# main-board_v1_23.net
KiCad netlist of a schematic drawn in EAGLE
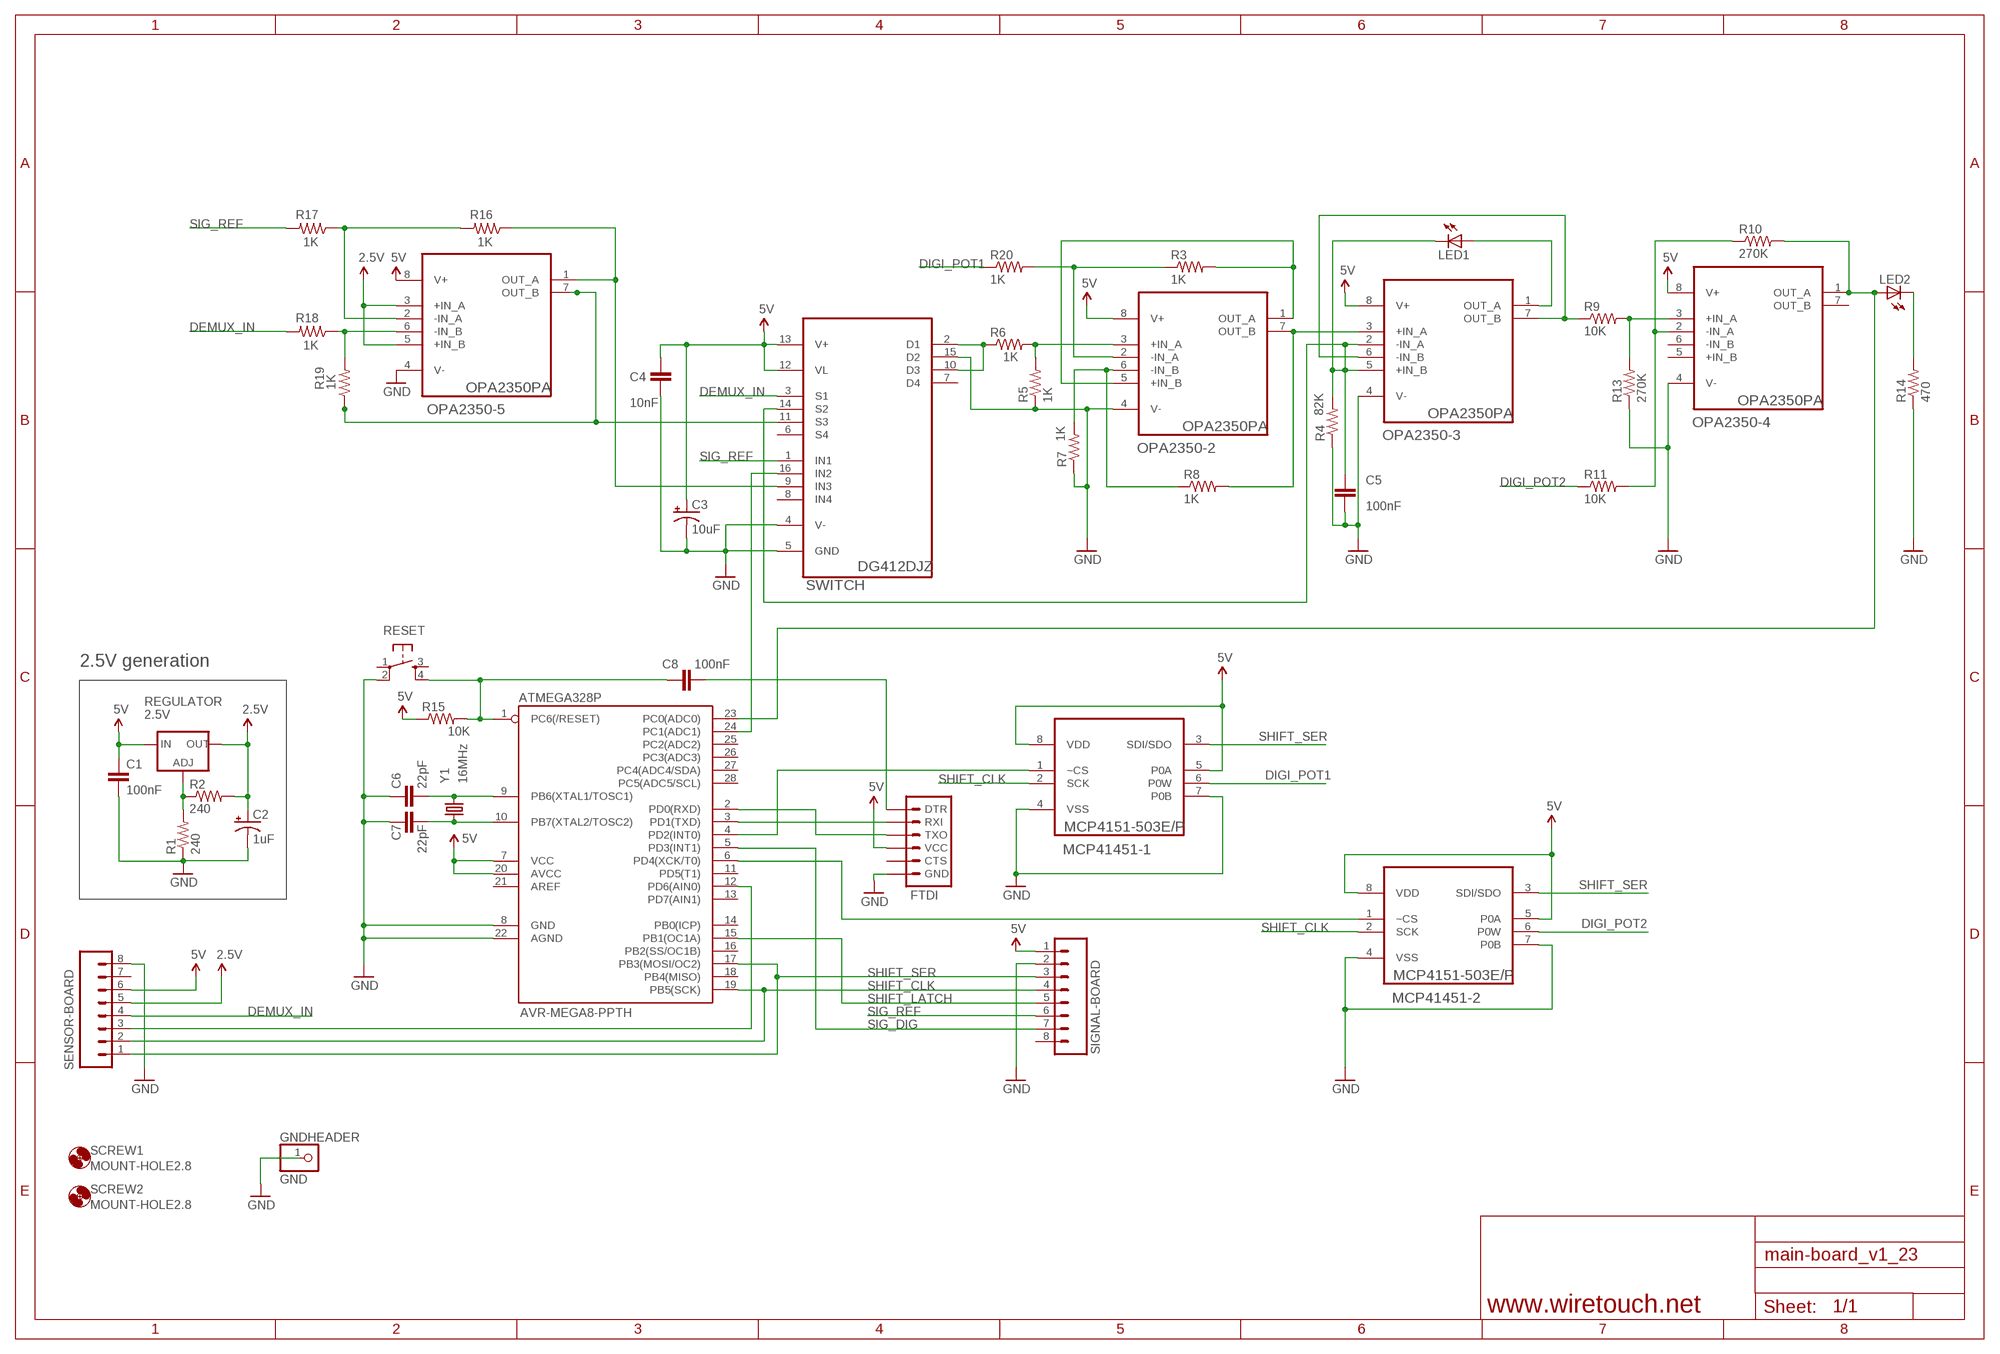
[diagram p0: schematic, sheet 1]

(export (version "E")
  (design (tool "Eeschema 10.0.6"))
  (components
    (comp (ref "ATMEGA328P")
      (value "AVR-MEGA8-PPTH")
      (footprint "eagle-import:DIL28-3")
      (libsource (lib "eagle-import") (part "AVR-MEGA8-PPTH"))
    )
    (comp (ref "C1")
      (value "100nF")
      (footprint "eagle-import:CAP-PTH-SMALL")
      (libsource (lib "eagle-import") (part "CAPPTH"))
    )
    (comp (ref "C2")
      (value "1uF")
      (footprint "eagle-import:CPOL-RADIAL-10UF-25V")
      (libsource (lib "eagle-import") (part "CAP_POLPTH2"))
    )
    (comp (ref "C3")
      (value "10uF")
      (footprint "eagle-import:CPOL-RADIAL-10UF-25V")
      (libsource (lib "eagle-import") (part "CAP_POLPTH2"))
    )
    (comp (ref "C4")
      (value "10nF")
      (footprint "eagle-import:CAP-PTH-SMALL")
      (libsource (lib "eagle-import") (part "CAPPTH"))
    )
    (comp (ref "C5")
      (value "100nF")
      (footprint "eagle-import:CAP-PTH-SMALL")
      (libsource (lib "eagle-import") (part "CAPPTH"))
    )
    (comp (ref "C6")
      (value "22pF")
      (footprint "eagle-import:CAP-PTH-SMALL2")
      (libsource (lib "eagle-import") (part "CAPPTH2"))
    )
    (comp (ref "C7")
      (value "22pF")
      (footprint "eagle-import:CAP-PTH-SMALL2")
      (libsource (lib "eagle-import") (part "CAPPTH2"))
    )
    (comp (ref "C8")
      (value "100nF")
      (footprint "eagle-import:CAP-PTH-SMALL2")
      (libsource (lib "eagle-import") (part "CAPPTH2"))
    )
    (comp (ref "FTDI")
      (value "ARDUINO_SERIAL_PROGRAMLONGPADS")
      (footprint "eagle-import:1X06_LONGPADS")
      (libsource (lib "eagle-import") (part "ARDUINO_SERIAL_PROGRAMLONGPADS"))
    )
    (comp (ref "GNDHEADER")
      (value "GND")
      (footprint "eagle-import:1X01")
      (libsource (lib "eagle-import") (part "PINHD-1X1"))
    )
    (comp (ref "LED1")
      (value "LED3MM")
      (footprint "eagle-import:LED3MM")
      (libsource (lib "eagle-import") (part "LED3MM"))
    )
    (comp (ref "LED2")
      (value "LED5MM")
      (footprint "eagle-import:LED5MM")
      (libsource (lib "eagle-import") (part "LED5MM"))
    )
    (comp (ref "MCP41451-1")
      (value "MCP4151-503E/P")
      (footprint "eagle-import:DIP254P762X533-8")
      (libsource (lib "eagle-import") (part "MCP4151-503E/P"))
    )
    (comp (ref "MCP41451-2")
      (value "MCP4151-503E/P")
      (footprint "eagle-import:DIP254P762X533-8")
      (libsource (lib "eagle-import") (part "MCP4151-503E/P"))
    )
    (comp (ref "OPA2350-2")
      (value "OPA2350PA")
      (footprint "eagle-import:DIP254P762X508-8")
      (libsource (lib "eagle-import") (part "OPA2350PA"))
    )
    (comp (ref "OPA2350-3")
      (value "OPA2350PA")
      (footprint "eagle-import:DIP254P762X508-8")
      (libsource (lib "eagle-import") (part "OPA2350PA"))
    )
    (comp (ref "OPA2350-4")
      (value "OPA2350PA")
      (footprint "eagle-import:DIP254P762X508-8")
      (libsource (lib "eagle-import") (part "OPA2350PA"))
    )
    (comp (ref "OPA2350-5")
      (value "OPA2350PA")
      (footprint "eagle-import:DIP254P762X508-8")
      (libsource (lib "eagle-import") (part "OPA2350PA"))
    )
    (comp (ref "R1")
      (value "240")
      (footprint "eagle-import:AXIAL-0.3")
      (libsource (lib "eagle-import") (part "RESISTORAXIAL-0.3"))
    )
    (comp (ref "R2")
      (value "240")
      (footprint "eagle-import:AXIAL-0.3")
      (libsource (lib "eagle-import") (part "RESISTORAXIAL-0.3"))
    )
    (comp (ref "R3")
      (value "1K")
      (footprint "eagle-import:AXIAL-0.3")
      (libsource (lib "eagle-import") (part "RESISTORAXIAL-0.3"))
    )
    (comp (ref "R4")
      (value "82K")
      (footprint "eagle-import:AXIAL-0.3")
      (libsource (lib "eagle-import") (part "RESISTORAXIAL-0.3"))
    )
    (comp (ref "R5")
      (value "1K")
      (footprint "eagle-import:AXIAL-0.3")
      (libsource (lib "eagle-import") (part "RESISTORAXIAL-0.3"))
    )
    (comp (ref "R6")
      (value "1K")
      (footprint "eagle-import:AXIAL-0.3")
      (libsource (lib "eagle-import") (part "RESISTORAXIAL-0.3"))
    )
    (comp (ref "R7")
      (value "1K")
      (footprint "eagle-import:AXIAL-0.3")
      (libsource (lib "eagle-import") (part "RESISTORAXIAL-0.3"))
    )
    (comp (ref "R8")
      (value "1K")
      (footprint "eagle-import:AXIAL-0.3")
      (libsource (lib "eagle-import") (part "RESISTORAXIAL-0.3"))
    )
    (comp (ref "R9")
      (value "10K")
      (footprint "eagle-import:AXIAL-0.3")
      (libsource (lib "eagle-import") (part "RESISTORAXIAL-0.3"))
    )
    (comp (ref "R10")
      (value "270K")
      (footprint "eagle-import:AXIAL-0.3")
      (libsource (lib "eagle-import") (part "RESISTORAXIAL-0.3"))
    )
    (comp (ref "R11")
      (value "10K")
      (footprint "eagle-import:AXIAL-0.3")
      (libsource (lib "eagle-import") (part "RESISTORAXIAL-0.3"))
    )
    (comp (ref "R13")
      (value "270K")
      (footprint "eagle-import:AXIAL-0.3")
      (libsource (lib "eagle-import") (part "RESISTORAXIAL-0.3"))
    )
    (comp (ref "R14")
      (value "470")
      (footprint "eagle-import:AXIAL-0.3")
      (libsource (lib "eagle-import") (part "RESISTORAXIAL-0.3"))
    )
    (comp (ref "R15")
      (value "10K")
      (footprint "eagle-import:AXIAL-0.3")
      (libsource (lib "eagle-import") (part "RESISTORAXIAL-0.3"))
    )
    (comp (ref "R16")
      (value "1K")
      (footprint "eagle-import:AXIAL-0.3")
      (libsource (lib "eagle-import") (part "RESISTORAXIAL-0.3"))
    )
    (comp (ref "R17")
      (value "1K")
      (footprint "eagle-import:AXIAL-0.3")
      (libsource (lib "eagle-import") (part "RESISTORAXIAL-0.3"))
    )
    (comp (ref "R18")
      (value "1K")
      (footprint "eagle-import:AXIAL-0.3")
      (libsource (lib "eagle-import") (part "RESISTORAXIAL-0.3"))
    )
    (comp (ref "R19")
      (value "1K")
      (footprint "eagle-import:AXIAL-0.3")
      (libsource (lib "eagle-import") (part "RESISTORAXIAL-0.3"))
    )
    (comp (ref "R20")
      (value "1K")
      (footprint "eagle-import:AXIAL-0.3")
      (libsource (lib "eagle-import") (part "RESISTORAXIAL-0.3"))
    )
    (comp (ref "REGULATOR")
      (value "2.5V")
      (footprint "eagle-import:TO220-ADJ")
      (libsource (lib "eagle-import") (part "V_REG_317SINK"))
    )
    (comp (ref "RESET")
      (value "Omron B3F momentary on switch")
      (footprint "eagle-import:TACTILE-PTH")
      (libsource (lib "eagle-import") (part "TAC_SWITCHPTH"))
    )
    (comp (ref "SCREW1")
      (value "MOUNT-HOLE2.8")
      (footprint "eagle-import:2,8")
      (libsource (lib "eagle-import") (part "MOUNT-HOLE2.8"))
    )
    (comp (ref "SCREW2")
      (value "MOUNT-HOLE2.8")
      (footprint "eagle-import:2,8")
      (libsource (lib "eagle-import") (part "MOUNT-HOLE2.8"))
    )
    (comp (ref "SENSOR-BOARD")
      (value "M08LONGPADS")
      (footprint "eagle-import:1X08_LONGPADS")
      (libsource (lib "eagle-import") (part "M08LONGPADS"))
    )
    (comp (ref "SIGNAL-BOARD")
      (value "M08LONGPADS")
      (footprint "eagle-import:1X08_LONGPADS")
      (libsource (lib "eagle-import") (part "M08LONGPADS"))
    )
    (comp (ref "SWITCH")
      (value "DG412DJZ")
      (footprint "eagle-import:DIP254P762X533-16")
      (libsource (lib "eagle-import") (part "DG412DJZ"))
    )
    (comp (ref "Y1")
      (value "16MHz")
      (footprint "eagle-import:HC49US")
      (libsource (lib "eagle-import") (part "CRYSTALHC49US"))
    )
  )
  (nets
    (net (code "1") (name "/DEMUX_IN") (class "Default")
      (node (ref "R18") (pin "P$2") (pinfunction "2_P$2") (pintype "passive"))
      (node (ref "SENSOR-BOARD") (pin "4") (pinfunction "4_4") (pintype "passive"))
      (node (ref "SWITCH") (pin "3") (pinfunction "S1_3") (pintype "input"))
    )
    (net (code "2") (name "/DIGI_POT1") (class "Default")
      (node (ref "MCP41451-1") (pin "6") (pinfunction "P0W_6") (pintype "passive"))
      (node (ref "R20") (pin "P$1") (pinfunction "1_P$1") (pintype "passive"))
    )
    (net (code "3") (name "/DIGI_POT2") (class "Default")
      (node (ref "MCP41451-2") (pin "6") (pinfunction "P0W_6") (pintype "passive"))
      (node (ref "R11") (pin "P$1") (pinfunction "1_P$1") (pintype "passive"))
    )
    (net (code "4") (name "/SHIFT_CLK") (class "Default")
      (node (ref "ATMEGA328P") (pin "19") (pinfunction "PB5(SCK)_19") (pintype "bidirectional"))
      (node (ref "MCP41451-1") (pin "2") (pinfunction "SCK_2") (pintype "input"))
      (node (ref "MCP41451-2") (pin "2") (pinfunction "SCK_2") (pintype "input"))
      (node (ref "SENSOR-BOARD") (pin "2") (pinfunction "2_2") (pintype "passive"))
      (node (ref "SIGNAL-BOARD") (pin "4") (pinfunction "4_4") (pintype "passive"))
    )
    (net (code "5") (name "/SHIFT_LATCH") (class "Default")
      (node (ref "ATMEGA328P") (pin "15") (pinfunction "PB1(OC1A)_15") (pintype "bidirectional"))
      (node (ref "SIGNAL-BOARD") (pin "5") (pinfunction "5_5") (pintype "passive"))
    )
    (net (code "6") (name "/SHIFT_SER") (class "Default")
      (node (ref "ATMEGA328P") (pin "17") (pinfunction "PB3(MOSI/OC2)_17") (pintype "bidirectional"))
      (node (ref "MCP41451-1") (pin "3") (pinfunction "SDI/SDO_3") (pintype "bidirectional"))
      (node (ref "MCP41451-2") (pin "3") (pinfunction "SDI/SDO_3") (pintype "bidirectional"))
      (node (ref "SENSOR-BOARD") (pin "1") (pinfunction "1_1") (pintype "passive"))
      (node (ref "SIGNAL-BOARD") (pin "3") (pinfunction "3_3") (pintype "passive"))
    )
    (net (code "7") (name "/SIG_DIG") (class "Default")
      (node (ref "ATMEGA328P") (pin "5") (pinfunction "PD3(INT1)_5") (pintype "bidirectional"))
      (node (ref "SIGNAL-BOARD") (pin "7") (pinfunction "7_7") (pintype "passive"))
    )
    (net (code "8") (name "/SIG_REF") (class "Default")
      (node (ref "R17") (pin "P$2") (pinfunction "2_P$2") (pintype "passive"))
      (node (ref "SIGNAL-BOARD") (pin "6") (pinfunction "6_6") (pintype "passive"))
      (node (ref "SWITCH") (pin "1") (pinfunction "IN1_1") (pintype "input"))
    )
    (net (code "9") (name "2.5V") (class "Default")
      (node (ref "C2") (pin "1") (pinfunction "+_1") (pintype "passive"))
      (node (ref "OPA2350-5") (pin "3") (pinfunction "+IN_A_3") (pintype "input"))
      (node (ref "OPA2350-5") (pin "5") (pinfunction "+IN_B_5") (pintype "input"))
      (node (ref "R2") (pin "P$2") (pinfunction "2_P$2") (pintype "passive"))
      (node (ref "REGULATOR") (pin "OUT") (pinfunction "OUT_OUT") (pintype "output"))
      (node (ref "SENSOR-BOARD") (pin "5") (pinfunction "5_5") (pintype "passive"))
    )
    (net (code "10") (name "5V") (class "Default")
      (node (ref "ATMEGA328P") (pin "20") (pinfunction "AVCC_20") (pintype "bidirectional"))
      (node (ref "ATMEGA328P") (pin "7") (pinfunction "VCC_7") (pintype "bidirectional"))
      (node (ref "C1") (pin "1") (pinfunction "1_1") (pintype "passive"))
      (node (ref "C3") (pin "1") (pinfunction "+_1") (pintype "passive"))
      (node (ref "C4") (pin "1") (pinfunction "1_1") (pintype "passive"))
      (node (ref "FTDI") (pin "4") (pinfunction "VCC_4") (pintype "passive"))
      (node (ref "MCP41451-1") (pin "5") (pinfunction "P0A_5") (pintype "passive"))
      (node (ref "MCP41451-1") (pin "8") (pinfunction "VDD_8") (pintype "power_in"))
      (node (ref "MCP41451-2") (pin "5") (pinfunction "P0A_5") (pintype "passive"))
      (node (ref "MCP41451-2") (pin "8") (pinfunction "VDD_8") (pintype "power_in"))
      (node (ref "OPA2350-2") (pin "8") (pinfunction "V+_8") (pintype "power_in"))
      (node (ref "OPA2350-3") (pin "8") (pinfunction "V+_8") (pintype "power_in"))
      (node (ref "OPA2350-4") (pin "8") (pinfunction "V+_8") (pintype "power_in"))
      (node (ref "OPA2350-5") (pin "8") (pinfunction "V+_8") (pintype "power_in"))
      (node (ref "R15") (pin "P$1") (pinfunction "1_P$1") (pintype "passive"))
      (node (ref "REGULATOR") (pin "IN") (pinfunction "IN_IN") (pintype "input"))
      (node (ref "SENSOR-BOARD") (pin "6") (pinfunction "6_6") (pintype "passive"))
      (node (ref "SIGNAL-BOARD") (pin "1") (pinfunction "1_1") (pintype "passive"))
      (node (ref "SWITCH") (pin "12") (pinfunction "VL_12") (pintype "power_in"))
      (node (ref "SWITCH") (pin "13") (pinfunction "V+_13") (pintype "power_in"))
    )
    (net (code "11") (name "GND") (class "Default")
      (node (ref "ATMEGA328P") (pin "22") (pinfunction "AGND_22") (pintype "bidirectional"))
      (node (ref "ATMEGA328P") (pin "8") (pinfunction "GND_8") (pintype "bidirectional"))
      (node (ref "C1") (pin "2") (pinfunction "2_2") (pintype "passive"))
      (node (ref "C2") (pin "2") (pinfunction "-_2") (pintype "passive"))
      (node (ref "C3") (pin "2") (pinfunction "-_2") (pintype "passive"))
      (node (ref "C4") (pin "2") (pinfunction "2_2") (pintype "passive"))
      (node (ref "C5") (pin "2") (pinfunction "2_2") (pintype "passive"))
      (node (ref "C6") (pin "1") (pinfunction "1_1") (pintype "passive"))
      (node (ref "C7") (pin "1") (pinfunction "1_1") (pintype "passive"))
      (node (ref "FTDI") (pin "6") (pinfunction "GND_6") (pintype "passive"))
      (node (ref "GNDHEADER") (pin "1") (pinfunction "1_1") (pintype "passive"))
      (node (ref "MCP41451-1") (pin "4") (pinfunction "VSS_4") (pintype "power_in"))
      (node (ref "MCP41451-1") (pin "7") (pinfunction "P0B_7") (pintype "passive"))
      (node (ref "MCP41451-2") (pin "4") (pinfunction "VSS_4") (pintype "power_in"))
      (node (ref "MCP41451-2") (pin "7") (pinfunction "P0B_7") (pintype "passive"))
      (node (ref "OPA2350-2") (pin "4") (pinfunction "V-_4") (pintype "power_in"))
      (node (ref "OPA2350-3") (pin "4") (pinfunction "V-_4") (pintype "power_in"))
      (node (ref "OPA2350-4") (pin "4") (pinfunction "V-_4") (pintype "power_in"))
      (node (ref "OPA2350-5") (pin "4") (pinfunction "V-_4") (pintype "power_in"))
      (node (ref "R1") (pin "P$1") (pinfunction "1_P$1") (pintype "passive"))
      (node (ref "R13") (pin "P$1") (pinfunction "1_P$1") (pintype "passive"))
      (node (ref "R14") (pin "P$1") (pinfunction "1_P$1") (pintype "passive"))
      (node (ref "R4") (pin "P$1") (pinfunction "1_P$1") (pintype "passive"))
      (node (ref "R5") (pin "P$1") (pinfunction "1_P$1") (pintype "passive"))
      (node (ref "R7") (pin "P$1") (pinfunction "1_P$1") (pintype "passive"))
      (node (ref "RESET") (pin "2") (pinfunction "2_2") (pintype "passive"))
      (node (ref "SENSOR-BOARD") (pin "8") (pinfunction "8_8") (pintype "passive"))
      (node (ref "SIGNAL-BOARD") (pin "2") (pinfunction "2_2") (pintype "passive"))
      (node (ref "SWITCH") (pin "15") (pinfunction "D2_15") (pintype "output"))
      (node (ref "SWITCH") (pin "4") (pinfunction "V-_4") (pintype "power_in"))
      (node (ref "SWITCH") (pin "5") (pinfunction "GND_5") (pintype "passive"))
    )
    (net (code "12") (name "Net-(ATMEGA328P-PB6(XTAL1{slash}TOSC1))") (class "Default")
      (node (ref "ATMEGA328P") (pin "9") (pinfunction "PB6(XTAL1/TOSC1)_9") (pintype "bidirectional"))
      (node (ref "C6") (pin "2") (pinfunction "2_2") (pintype "passive"))
      (node (ref "Y1") (pin "2") (pinfunction "2_2") (pintype "passive"))
    )
    (net (code "13") (name "Net-(ATMEGA328P-PB7(XTAL2{slash}TOSC2))") (class "Default")
      (node (ref "ATMEGA328P") (pin "10") (pinfunction "PB7(XTAL2/TOSC2)_10") (pintype "bidirectional"))
      (node (ref "C7") (pin "2") (pinfunction "2_2") (pintype "passive"))
      (node (ref "Y1") (pin "1") (pinfunction "1_1") (pintype "passive"))
    )
    (net (code "14") (name "Net-(ATMEGA328P-PC0(ADC0))") (class "Default")
      (node (ref "ATMEGA328P") (pin "23") (pinfunction "PC0(ADC0)_23") (pintype "bidirectional"))
      (node (ref "LED2") (pin "A") (pinfunction "A_A") (pintype "passive"))
      (node (ref "OPA2350-4") (pin "1") (pinfunction "OUT_A_1") (pintype "output"))
      (node (ref "R10") (pin "P$2") (pinfunction "2_P$2") (pintype "passive"))
    )
    (net (code "15") (name "Net-(ATMEGA328P-PC1(ADC1))") (class "Default")
      (node (ref "ATMEGA328P") (pin "24") (pinfunction "PC1(ADC1)_24") (pintype "bidirectional"))
      (node (ref "SWITCH") (pin "16") (pinfunction "IN2_16") (pintype "input"))
    )
    (net (code "16") (name "Net-(ATMEGA328P-PC6({slash}RESET))") (class "Default")
      (node (ref "ATMEGA328P") (pin "1") (pinfunction "PC6(/RESET)_1") (pintype "bidirectional"))
      (node (ref "C8") (pin "1") (pinfunction "1_1") (pintype "passive"))
      (node (ref "R15") (pin "P$2") (pinfunction "2_P$2") (pintype "passive"))
      (node (ref "RESET") (pin "4") (pinfunction "4_4") (pintype "passive"))
    )
    (net (code "17") (name "Net-(ATMEGA328P-PD0(RXD))") (class "Default")
      (node (ref "ATMEGA328P") (pin "2") (pinfunction "PD0(RXD)_2") (pintype "bidirectional"))
      (node (ref "FTDI") (pin "3") (pinfunction "TXO_3") (pintype "passive"))
    )
    (net (code "18") (name "Net-(ATMEGA328P-PD1(TXD))") (class "Default")
      (node (ref "ATMEGA328P") (pin "3") (pinfunction "PD1(TXD)_3") (pintype "bidirectional"))
      (node (ref "FTDI") (pin "2") (pinfunction "RXI_2") (pintype "passive"))
    )
    (net (code "19") (name "Net-(ATMEGA328P-PD2(INT0))") (class "Default")
      (node (ref "ATMEGA328P") (pin "4") (pinfunction "PD2(INT0)_4") (pintype "bidirectional"))
      (node (ref "MCP41451-1") (pin "1") (pinfunction "~{CS}_1") (pintype "input"))
    )
    (net (code "20") (name "Net-(ATMEGA328P-PD4(XCK{slash}T0))") (class "Default")
      (node (ref "ATMEGA328P") (pin "6") (pinfunction "PD4(XCK/T0)_6") (pintype "bidirectional"))
      (node (ref "MCP41451-2") (pin "1") (pinfunction "~{CS}_1") (pintype "input"))
    )
    (net (code "21") (name "Net-(ATMEGA328P-PD6(AIN0))") (class "Default")
      (node (ref "ATMEGA328P") (pin "12") (pinfunction "PD6(AIN0)_12") (pintype "bidirectional"))
      (node (ref "SENSOR-BOARD") (pin "3") (pinfunction "3_3") (pintype "passive"))
    )
    (net (code "22") (name "Net-(FTDI-DTR)") (class "Default")
      (node (ref "C8") (pin "2") (pinfunction "2_2") (pintype "passive"))
      (node (ref "FTDI") (pin "1") (pinfunction "DTR_1") (pintype "passive"))
    )
    (net (code "23") (name "Net-(LED1-C)") (class "Default")
      (node (ref "C5") (pin "1") (pinfunction "1_1") (pintype "passive"))
      (node (ref "LED1") (pin "K") (pinfunction "C_K") (pintype "passive"))
      (node (ref "OPA2350-3") (pin "2") (pinfunction "-IN_A_2") (pintype "input"))
      (node (ref "OPA2350-3") (pin "5") (pinfunction "+IN_B_5") (pintype "input"))
      (node (ref "R4") (pin "P$2") (pinfunction "2_P$2") (pintype "passive"))
      (node (ref "SWITCH") (pin "14") (pinfunction "S2_14") (pintype "input"))
    )
    (net (code "24") (name "Net-(LED2-C)") (class "Default")
      (node (ref "LED2") (pin "K") (pinfunction "C_K") (pintype "passive"))
      (node (ref "R14") (pin "P$2") (pinfunction "2_P$2") (pintype "passive"))
    )
    (net (code "25") (name "Net-(OPA2350-2-+IN_A)") (class "Default")
      (node (ref "OPA2350-2") (pin "3") (pinfunction "+IN_A_3") (pintype "input"))
      (node (ref "R5") (pin "P$2") (pinfunction "2_P$2") (pintype "passive"))
      (node (ref "R6") (pin "P$2") (pinfunction "2_P$2") (pintype "passive"))
    )
    (net (code "26") (name "Net-(OPA2350-2-+IN_B)") (class "Default")
      (node (ref "OPA2350-2") (pin "1") (pinfunction "OUT_A_1") (pintype "output"))
      (node (ref "OPA2350-2") (pin "5") (pinfunction "+IN_B_5") (pintype "input"))
      (node (ref "R3") (pin "P$2") (pinfunction "2_P$2") (pintype "passive"))
    )
    (net (code "27") (name "Net-(OPA2350-2--IN_A)") (class "Default")
      (node (ref "OPA2350-2") (pin "2") (pinfunction "-IN_A_2") (pintype "input"))
      (node (ref "R20") (pin "P$2") (pinfunction "2_P$2") (pintype "passive"))
      (node (ref "R3") (pin "P$1") (pinfunction "1_P$1") (pintype "passive"))
    )
    (net (code "28") (name "Net-(OPA2350-2--IN_B)") (class "Default")
      (node (ref "OPA2350-2") (pin "6") (pinfunction "-IN_B_6") (pintype "input"))
      (node (ref "R7") (pin "P$2") (pinfunction "2_P$2") (pintype "passive"))
      (node (ref "R8") (pin "P$1") (pinfunction "1_P$1") (pintype "passive"))
    )
    (net (code "29") (name "Net-(OPA2350-2-OUT_B)") (class "Default")
      (node (ref "OPA2350-2") (pin "7") (pinfunction "OUT_B_7") (pintype "output"))
      (node (ref "OPA2350-3") (pin "3") (pinfunction "+IN_A_3") (pintype "input"))
      (node (ref "R8") (pin "P$2") (pinfunction "2_P$2") (pintype "passive"))
    )
    (net (code "30") (name "Net-(OPA2350-3--IN_B)") (class "Default")
      (node (ref "OPA2350-3") (pin "6") (pinfunction "-IN_B_6") (pintype "input"))
      (node (ref "OPA2350-3") (pin "7") (pinfunction "OUT_B_7") (pintype "output"))
      (node (ref "R9") (pin "P$1") (pinfunction "1_P$1") (pintype "passive"))
    )
    (net (code "31") (name "Net-(OPA2350-3-OUT_A)") (class "Default")
      (node (ref "LED1") (pin "A") (pinfunction "A_A") (pintype "passive"))
      (node (ref "OPA2350-3") (pin "1") (pinfunction "OUT_A_1") (pintype "output"))
    )
    (net (code "32") (name "Net-(OPA2350-4-+IN_A)") (class "Default")
      (node (ref "OPA2350-4") (pin "3") (pinfunction "+IN_A_3") (pintype "input"))
      (node (ref "R13") (pin "P$2") (pinfunction "2_P$2") (pintype "passive"))
      (node (ref "R9") (pin "P$2") (pinfunction "2_P$2") (pintype "passive"))
    )
    (net (code "33") (name "Net-(OPA2350-4--IN_A)") (class "Default")
      (node (ref "OPA2350-4") (pin "2") (pinfunction "-IN_A_2") (pintype "input"))
      (node (ref "R10") (pin "P$1") (pinfunction "1_P$1") (pintype "passive"))
      (node (ref "R11") (pin "P$2") (pinfunction "2_P$2") (pintype "passive"))
    )
    (net (code "34") (name "Net-(OPA2350-5--IN_A)") (class "Default")
      (node (ref "OPA2350-5") (pin "2") (pinfunction "-IN_A_2") (pintype "input"))
      (node (ref "R16") (pin "P$2") (pinfunction "2_P$2") (pintype "passive"))
      (node (ref "R17") (pin "P$1") (pinfunction "1_P$1") (pintype "passive"))
    )
    (net (code "35") (name "Net-(OPA2350-5--IN_B)") (class "Default")
      (node (ref "OPA2350-5") (pin "6") (pinfunction "-IN_B_6") (pintype "input"))
      (node (ref "R18") (pin "P$1") (pinfunction "1_P$1") (pintype "passive"))
      (node (ref "R19") (pin "P$2") (pinfunction "2_P$2") (pintype "passive"))
    )
    (net (code "36") (name "Net-(OPA2350-5-OUT_A)") (class "Default")
      (node (ref "OPA2350-5") (pin "1") (pinfunction "OUT_A_1") (pintype "output"))
      (node (ref "R16") (pin "P$1") (pinfunction "1_P$1") (pintype "passive"))
      (node (ref "SWITCH") (pin "9") (pinfunction "IN3_9") (pintype "input"))
    )
    (net (code "37") (name "Net-(OPA2350-5-OUT_B)") (class "Default")
      (node (ref "OPA2350-5") (pin "7") (pinfunction "OUT_B_7") (pintype "output"))
      (node (ref "R19") (pin "P$1") (pinfunction "1_P$1") (pintype "passive"))
      (node (ref "SWITCH") (pin "11") (pinfunction "S3_11") (pintype "input"))
    )
    (net (code "38") (name "Net-(R1-2)") (class "Default")
      (node (ref "R1") (pin "P$2") (pinfunction "2_P$2") (pintype "passive"))
      (node (ref "R2") (pin "P$1") (pinfunction "1_P$1") (pintype "passive"))
      (node (ref "REGULATOR") (pin "ADJ") (pinfunction "ADJ_ADJ") (pintype "input"))
    )
    (net (code "39") (name "Net-(R6-1)") (class "Default")
      (node (ref "R6") (pin "P$1") (pinfunction "1_P$1") (pintype "passive"))
      (node (ref "SWITCH") (pin "10") (pinfunction "D3_10") (pintype "output"))
      (node (ref "SWITCH") (pin "2") (pinfunction "D1_2") (pintype "output"))
    )
    (net (code "40") (name "unconnected-(ATMEGA328P-AREF-Pad21)") (class "Default")
      (node (ref "ATMEGA328P") (pin "21") (pinfunction "AREF_21") (pintype "bidirectional"))
    )
    (net (code "41") (name "unconnected-(ATMEGA328P-PB0(ICP)-Pad14)") (class "Default")
      (node (ref "ATMEGA328P") (pin "14") (pinfunction "PB0(ICP)_14") (pintype "bidirectional"))
    )
    (net (code "42") (name "unconnected-(ATMEGA328P-PB2(SS{slash}OC1B)-Pad16)") (class "Default")
      (node (ref "ATMEGA328P") (pin "16") (pinfunction "PB2(SS/OC1B)_16") (pintype "bidirectional"))
    )
    (net (code "43") (name "unconnected-(ATMEGA328P-PB4(MISO)-Pad18)") (class "Default")
      (node (ref "ATMEGA328P") (pin "18") (pinfunction "PB4(MISO)_18") (pintype "bidirectional"))
    )
    (net (code "44") (name "unconnected-(ATMEGA328P-PC2(ADC2)-Pad25)") (class "Default")
      (node (ref "ATMEGA328P") (pin "25") (pinfunction "PC2(ADC2)_25") (pintype "bidirectional"))
    )
    (net (code "45") (name "unconnected-(ATMEGA328P-PC3(ADC3)-Pad26)") (class "Default")
      (node (ref "ATMEGA328P") (pin "26") (pinfunction "PC3(ADC3)_26") (pintype "bidirectional"))
    )
    (net (code "46") (name "unconnected-(ATMEGA328P-PC4(ADC4{slash}SDA)-Pad27)") (class "Default")
      (node (ref "ATMEGA328P") (pin "27") (pinfunction "PC4(ADC4/SDA)_27") (pintype "bidirectional"))
    )
    (net (code "47") (name "unconnected-(ATMEGA328P-PC5(ADC5{slash}SCL)-Pad28)") (class "Default")
      (node (ref "ATMEGA328P") (pin "28") (pinfunction "PC5(ADC5/SCL)_28") (pintype "bidirectional"))
    )
    (net (code "48") (name "unconnected-(ATMEGA328P-PD5(T1)-Pad11)") (class "Default")
      (node (ref "ATMEGA328P") (pin "11") (pinfunction "PD5(T1)_11") (pintype "bidirectional"))
    )
    (net (code "49") (name "unconnected-(ATMEGA328P-PD7(AIN1)-Pad13)") (class "Default")
      (node (ref "ATMEGA328P") (pin "13") (pinfunction "PD7(AIN1)_13") (pintype "bidirectional"))
    )
    (net (code "50") (name "unconnected-(FTDI-CTS-Pad5)") (class "Default")
      (node (ref "FTDI") (pin "5") (pinfunction "CTS_5") (pintype "passive"))
    )
    (net (code "51") (name "unconnected-(OPA2350-4-+IN_B-Pad5)") (class "Default")
      (node (ref "OPA2350-4") (pin "5") (pinfunction "+IN_B_5") (pintype "input"))
    )
    (net (code "52") (name "unconnected-(OPA2350-4--IN_B-Pad6)") (class "Default")
      (node (ref "OPA2350-4") (pin "6") (pinfunction "-IN_B_6") (pintype "input"))
    )
    (net (code "53") (name "unconnected-(OPA2350-4-OUT_B-Pad7)") (class "Default")
      (node (ref "OPA2350-4") (pin "7") (pinfunction "OUT_B_7") (pintype "output"))
    )
    (net (code "54") (name "unconnected-(RESET-Pad1)") (class "Default")
      (node (ref "RESET") (pin "1") (pinfunction "1_1") (pintype "passive"))
    )
    (net (code "55") (name "unconnected-(RESET-Pad3)") (class "Default")
      (node (ref "RESET") (pin "3") (pinfunction "3_3") (pintype "passive"))
    )
    (net (code "56") (name "unconnected-(SENSOR-BOARD-Pad7)") (class "Default")
      (node (ref "SENSOR-BOARD") (pin "7") (pinfunction "7_7") (pintype "passive"))
    )
    (net (code "57") (name "unconnected-(SIGNAL-BOARD-Pad8)") (class "Default")
      (node (ref "SIGNAL-BOARD") (pin "8") (pinfunction "8_8") (pintype "passive"))
    )
    (net (code "58") (name "unconnected-(SWITCH-D4-Pad7)") (class "Default")
      (node (ref "SWITCH") (pin "7") (pinfunction "D4_7") (pintype "output"))
    )
    (net (code "59") (name "unconnected-(SWITCH-IN4-Pad8)") (class "Default")
      (node (ref "SWITCH") (pin "8") (pinfunction "IN4_8") (pintype "input"))
    )
    (net (code "60") (name "unconnected-(SWITCH-S4-Pad6)") (class "Default")
      (node (ref "SWITCH") (pin "6") (pinfunction "S4_6") (pintype "input"))
    )
  )
)
